# mcu.net
KiCad netlist of a schematic drawn in Altium Designer
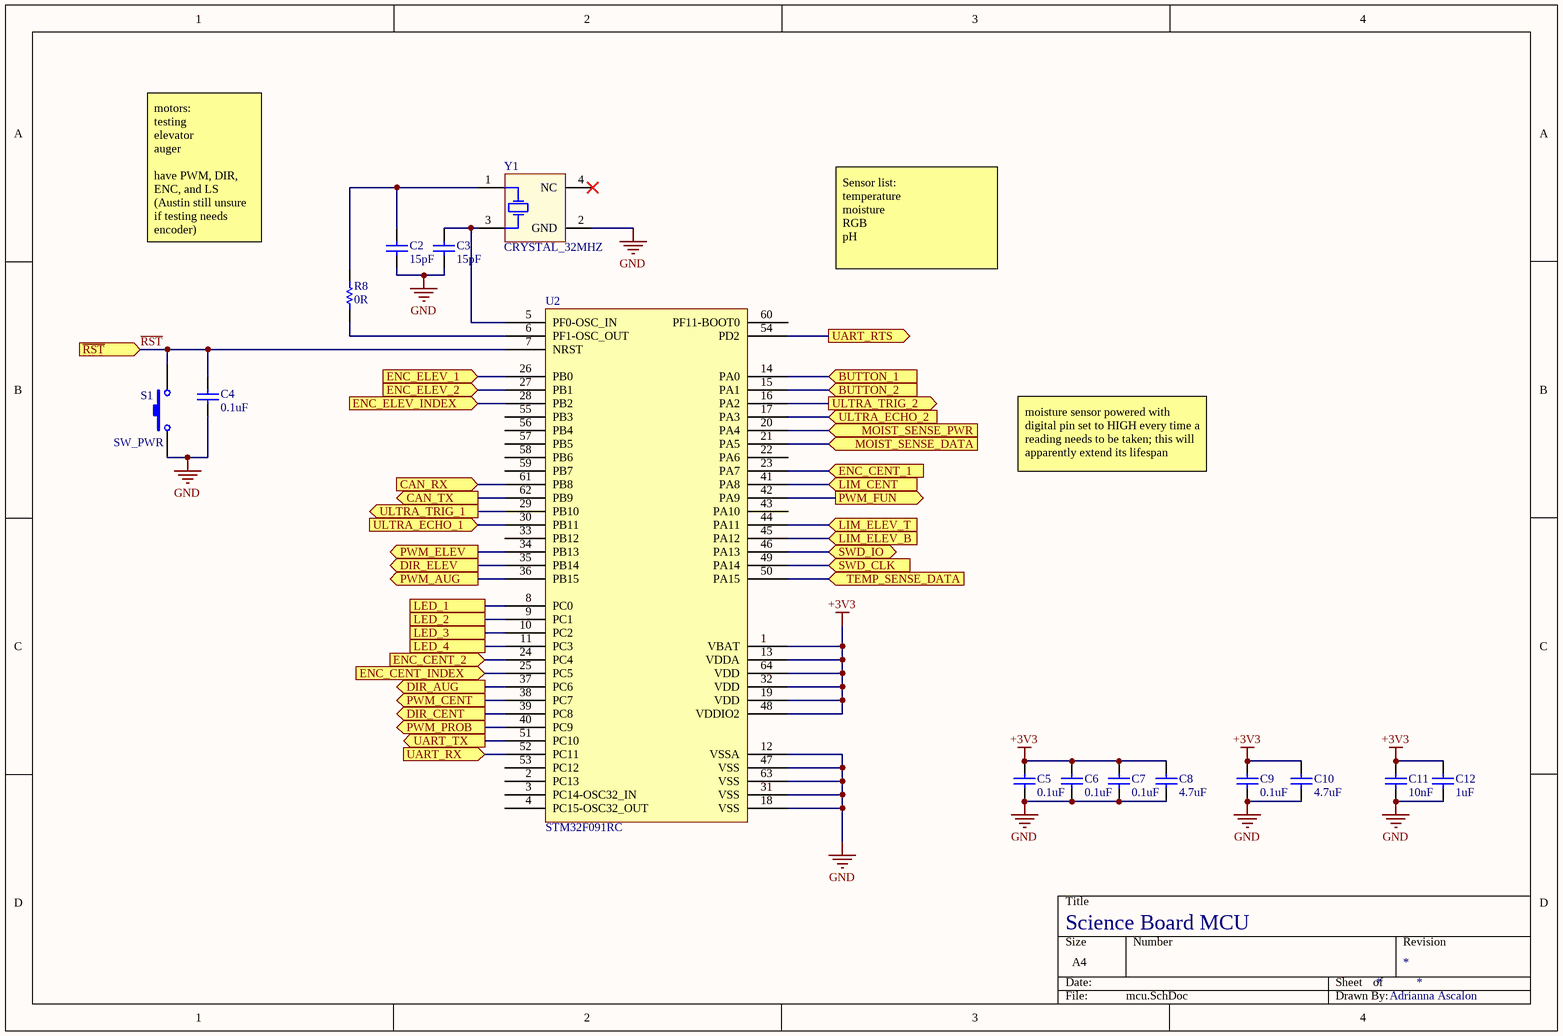
[diagram p0: mcu.SchDoc]

(export (version "E")
  (design (tool "Eeschema 10.0.6"))
  (components
    (comp (ref "C2")
      (value "15pF")
      (footprint "CAPC0603(1608)55_N")
      (description "CAP CER 15PF 250V NPO 0603")
      (fields (field (name "MANUFACTURER") "Yageo") (field (name "MPN") "AC0603JRNPOYBN150"))
      (libsource (lib "UWRT_Schematic_Library_2019") (part "CAP_15pF_0603"))
    )
    (comp (ref "C3")
      (value "15pF")
      (footprint "CAPC0603(1608)55_N")
      (description "CAP CER 15PF 250V NPO 0603")
      (fields (field (name "MANUFACTURER") "Yageo") (field (name "MPN") "AC0603JRNPOYBN150"))
      (libsource (lib "UWRT_Schematic_Library_2019") (part "CAP_15pF_0603"))
    )
    (comp (ref "C4")
      (value "0.1uF")
      (footprint "CAPC0603(1608)55_N")
      (description "CAP CER 0.1UF 16V X7R 0603")
      (fields (field (name "MANUFACTURER") "Yageo") (field (name "MPN") "CC0603KRX7R7BB104"))
      (libsource (lib "UWRT_Schematic_Library_2019") (part "CAP_0.1uF_16V_0603"))
    )
    (comp (ref "C5")
      (value "0.1uF")
      (footprint "CAPC0603(1608)55_N")
      (description "CAP CER 0.1UF 16V X7R 0603")
      (fields (field (name "MANUFACTURER") "Yageo") (field (name "MPN") "CC0603KRX7R7BB104"))
      (libsource (lib "UWRT_Schematic_Library_2019") (part "CAP_0.1uF_16V_0603"))
    )
    (comp (ref "C6")
      (value "0.1uF")
      (footprint "CAPC0603(1608)55_N")
      (description "CAP CER 0.1UF 16V X7R 0603")
      (fields (field (name "MANUFACTURER") "Yageo") (field (name "MPN") "CC0603KRX7R7BB104"))
      (libsource (lib "UWRT_Schematic_Library_2019") (part "CAP_0.1uF_16V_0603"))
    )
    (comp (ref "C7")
      (value "0.1uF")
      (footprint "CAPC0603(1608)55_N")
      (description "CAP CER 0.1UF 16V X7R 0603")
      (fields (field (name "MANUFACTURER") "Yageo") (field (name "MPN") "CC0603KRX7R7BB104"))
      (libsource (lib "UWRT_Schematic_Library_2019") (part "CAP_0.1uF_16V_0603"))
    )
    (comp (ref "C8")
      (value "4.7uF")
      (footprint "CAPC0603(1608)55_N")
      (description "CAP CER 4.7UF 6.3V X5R 0603")
      (fields (field (name "MANUFACTURER") "Yageo") (field (name "MPN") "CC0603KRX5R5BB475"))
      (libsource (lib "UWRT_Schematic_Library_2019") (part "CAP_4.7uF_0603"))
    )
    (comp (ref "C9")
      (value "0.1uF")
      (footprint "CAPC0603(1608)55_N")
      (description "CAP CER 0.1UF 16V X7R 0603")
      (fields (field (name "MANUFACTURER") "Yageo") (field (name "MPN") "CC0603KRX7R7BB104"))
      (libsource (lib "UWRT_Schematic_Library_2019") (part "CAP_0.1uF_16V_0603"))
    )
    (comp (ref "C10")
      (value "4.7uF")
      (footprint "CAPC0603(1608)55_N")
      (description "CAP CER 4.7UF 6.3V X5R 0603")
      (fields (field (name "MANUFACTURER") "Yageo") (field (name "MPN") "CC0603KRX5R5BB475"))
      (libsource (lib "UWRT_Schematic_Library_2019") (part "CAP_4.7uF_0603"))
    )
    (comp (ref "C11")
      (value "10nF")
      (footprint "CAPC0603(1608)55_N")
      (description "CAP CER 10000PF 16V X7R 0603")
      (fields (field (name "MANUFACTURER") "Yageo") (field (name "MPN") "CC0603KRX7R7BB103"))
      (libsource (lib "UWRT_Schematic_Library_2019") (part "CAP_10nF_0603"))
    )
    (comp (ref "C12")
      (value "1uF")
      (footprint "CAPC0603(1608)55_N")
      (description "CAP CER 1UF 16V Y5V 0603")
      (fields (field (name "MANUFACTURER") "Yageo") (field (name "MPN") "CC0603ZRY5V7BB105"))
      (libsource (lib "UWRT_Schematic_Library_2019") (part "CAP_1uF_16V_0603"))
    )
    (comp (ref "R8")
      (value "0R")
      (footprint "RESC0603(1608)_N")
      (description "RES SMD 0 OHM JUMPER 1/10W 0603")
      (fields (field (name "MANUFACTURER") "Yageo") (field (name "MPN") "RC0603JR-070RL"))
      (libsource (lib "UWRT_Schematic_Library_2019") (part "RES_0R_0603"))
    )
    (comp (ref "S1")
      (value "SW_PWR")
      (footprint "PTS830GM140")
      (description "Power Switch (Red)")
      (fields
        (field (name "MPN") "PTS830GM140 SMTR LFS")
        (field (name "DIGIKEY PART NUMBER") "CKN10587CT-ND")
      )
      (libsource (lib "UWRT_Schematic_Library_2019") (part "SW_PWR"))
    )
    (comp (ref "U2")
      (value "STM32F091RC")
      (footprint "UWRT_Footprint_Library_2019:STM_LQFP64_N")
      (fields
        (field (name "MANUFACTURER") "STMicroelectronics")
        (field (name "DIGIKEY PART NUMBER") "497-15167-ND")
      )
      (libsource (lib "UWRT_Schematic_Library_2019") (part "STM32F091RC"))
    )
    (comp (ref "Y1")
      (value "CRYSTAL_32MHZ")
      (footprint "AVX-CX2520DB32000D0GEJZ1-4_V")
      (description "CRYSTAL 32MHZ 8PF SMD")
      (fields
        (field (name "MANUFACTURER") "Kyocera International Inc. Electronic Components")
        (field (name "MPN") "CX2520DB32000D0GPSC1")
      )
      (libsource (lib "UWRT_Schematic_Library_2019") (part "CRYSTAL_32MHZ"))
    )
  )
  (nets
    (net (code "1") (name "+3V3") (class "Default")
      (node (ref "C10") (pin "2") (pinfunction "2_2") (pintype "passive"))
      (node (ref "C11") (pin "2") (pinfunction "2_2") (pintype "passive"))
      (node (ref "C12") (pin "2") (pinfunction "2_2") (pintype "passive"))
      (node (ref "C5") (pin "1") (pinfunction "1_1") (pintype "passive"))
      (node (ref "C6") (pin "1") (pinfunction "1_1") (pintype "passive"))
      (node (ref "C7") (pin "1") (pinfunction "1_1") (pintype "passive"))
      (node (ref "C8") (pin "2") (pinfunction "2_2") (pintype "passive"))
      (node (ref "C9") (pin "1") (pinfunction "1_1") (pintype "passive"))
      (node (ref "U2") (pin "1") (pinfunction "VBAT_1") (pintype "passive"))
      (node (ref "U2") (pin "13") (pinfunction "VDDA_13") (pintype "passive"))
      (node (ref "U2") (pin "19") (pinfunction "VDD_19") (pintype "passive"))
      (node (ref "U2") (pin "32") (pinfunction "VDD_32") (pintype "passive"))
      (node (ref "U2") (pin "48") (pinfunction "VDDIO2_48") (pintype "passive"))
      (node (ref "U2") (pin "64") (pinfunction "VDD_64") (pintype "passive"))
    )
    (net (code "2") (name "/BUTTON_1") (class "Default")
      (node (ref "U2") (pin "14") (pinfunction "PA0_14") (pintype "passive"))
    )
    (net (code "3") (name "/BUTTON_2") (class "Default")
      (node (ref "U2") (pin "15") (pinfunction "PA1_15") (pintype "passive"))
    )
    (net (code "4") (name "/CAN_RX") (class "Default")
      (node (ref "U2") (pin "61") (pinfunction "PB8_61") (pintype "passive"))
    )
    (net (code "5") (name "/CAN_TX") (class "Default")
      (node (ref "U2") (pin "62") (pinfunction "PB9_62") (pintype "passive"))
    )
    (net (code "6") (name "/DIR_AUG") (class "Default")
      (node (ref "U2") (pin "37") (pinfunction "PC6_37") (pintype "passive"))
    )
    (net (code "7") (name "/DIR_CENT") (class "Default")
      (node (ref "U2") (pin "39") (pinfunction "PC8_39") (pintype "passive"))
    )
    (net (code "8") (name "/DIR_ELEV") (class "Default")
      (node (ref "U2") (pin "35") (pinfunction "PB14_35") (pintype "passive"))
    )
    (net (code "9") (name "/ENC_CENT_1") (class "Default")
      (node (ref "U2") (pin "23") (pinfunction "PA7_23") (pintype "passive"))
    )
    (net (code "10") (name "/ENC_CENT_2") (class "Default")
      (node (ref "U2") (pin "24") (pinfunction "PC4_24") (pintype "passive"))
    )
    (net (code "11") (name "/ENC_CENT_INDEX") (class "Default")
      (node (ref "U2") (pin "25") (pinfunction "PC5_25") (pintype "passive"))
    )
    (net (code "12") (name "/ENC_ELEV_1") (class "Default")
      (node (ref "U2") (pin "26") (pinfunction "PB0_26") (pintype "passive"))
    )
    (net (code "13") (name "/ENC_ELEV_2") (class "Default")
      (node (ref "U2") (pin "27") (pinfunction "PB1_27") (pintype "passive"))
    )
    (net (code "14") (name "/ENC_ELEV_INDEX") (class "Default")
      (node (ref "U2") (pin "28") (pinfunction "PB2_28") (pintype "passive"))
    )
    (net (code "15") (name "/LED_1") (class "Default")
      (node (ref "U2") (pin "8") (pinfunction "PC0_8") (pintype "passive"))
    )
    (net (code "16") (name "/LED_2") (class "Default")
      (node (ref "U2") (pin "9") (pinfunction "PC1_9") (pintype "passive"))
    )
    (net (code "17") (name "/LED_3") (class "Default")
      (node (ref "U2") (pin "10") (pinfunction "PC2_10") (pintype "passive"))
    )
    (net (code "18") (name "/LED_4") (class "Default")
      (node (ref "U2") (pin "11") (pinfunction "PC3_11") (pintype "passive"))
    )
    (net (code "19") (name "/LIM_CENT") (class "Default")
      (node (ref "U2") (pin "41") (pinfunction "PA8_41") (pintype "passive"))
    )
    (net (code "20") (name "/LIM_ELEV_B") (class "Default")
      (node (ref "U2") (pin "45") (pinfunction "PA12_45") (pintype "passive"))
    )
    (net (code "21") (name "/LIM_ELEV_T") (class "Default")
      (node (ref "U2") (pin "44") (pinfunction "PA11_44") (pintype "passive"))
    )
    (net (code "22") (name "/MOIST_SENSE_DATA") (class "Default")
      (node (ref "U2") (pin "21") (pinfunction "PA5_21") (pintype "passive"))
    )
    (net (code "23") (name "/MOIST_SENSE_PWR") (class "Default")
      (node (ref "U2") (pin "20") (pinfunction "PA4_20") (pintype "passive"))
    )
    (net (code "24") (name "/PWM_AUG") (class "Default")
      (node (ref "U2") (pin "36") (pinfunction "PB15_36") (pintype "passive"))
    )
    (net (code "25") (name "/PWM_CENT") (class "Default")
      (node (ref "U2") (pin "38") (pinfunction "PC7_38") (pintype "passive"))
    )
    (net (code "26") (name "/PWM_ELEV") (class "Default")
      (node (ref "U2") (pin "34") (pinfunction "PB13_34") (pintype "passive"))
    )
    (net (code "27") (name "/PWM_FUN") (class "Default")
      (node (ref "U2") (pin "42") (pinfunction "PA9_42") (pintype "passive"))
    )
    (net (code "28") (name "/PWM_PROB") (class "Default")
      (node (ref "U2") (pin "40") (pinfunction "PC9_40") (pintype "passive"))
    )
    (net (code "29") (name "/SWD_CLK") (class "Default")
      (node (ref "U2") (pin "49") (pinfunction "PA14_49") (pintype "passive"))
    )
    (net (code "30") (name "/SWD_IO") (class "Default")
      (node (ref "U2") (pin "46") (pinfunction "PA13_46") (pintype "passive"))
    )
    (net (code "31") (name "/TEMP_SENSE_DATA") (class "Default")
      (node (ref "U2") (pin "50") (pinfunction "PA15_50") (pintype "passive"))
    )
    (net (code "32") (name "/UART_RTS") (class "Default")
      (node (ref "U2") (pin "54") (pinfunction "PD2_54") (pintype "passive"))
    )
    (net (code "33") (name "/UART_RX") (class "Default")
      (node (ref "U2") (pin "52") (pinfunction "PC11_52") (pintype "passive"))
    )
    (net (code "34") (name "/UART_TX") (class "Default")
      (node (ref "U2") (pin "51") (pinfunction "PC10_51") (pintype "passive"))
    )
    (net (code "35") (name "/ULTRA_ECHO_1") (class "Default")
      (node (ref "U2") (pin "30") (pinfunction "PB11_30") (pintype "passive"))
    )
    (net (code "36") (name "/ULTRA_ECHO_2") (class "Default")
      (node (ref "U2") (pin "17") (pinfunction "PA3_17") (pintype "passive"))
    )
    (net (code "37") (name "/ULTRA_TRIG_1") (class "Default")
      (node (ref "U2") (pin "29") (pinfunction "PB10_29") (pintype "passive"))
    )
    (net (code "38") (name "/ULTRA_TRIG_2") (class "Default")
      (node (ref "U2") (pin "16") (pinfunction "PA2_16") (pintype "passive"))
    )
    (net (code "39") (name "/~{RST}") (class "Default")
      (node (ref "C4") (pin "2") (pinfunction "2_2") (pintype "passive"))
      (node (ref "S1") (pin "2") (pinfunction "2_2") (pintype "passive"))
      (node (ref "U2") (pin "7") (pinfunction "NRST_7") (pintype "passive"))
    )
    (net (code "40") (name "GND") (class "Default")
      (node (ref "C10") (pin "1") (pinfunction "1_1") (pintype "passive"))
      (node (ref "C11") (pin "1") (pinfunction "1_1") (pintype "passive"))
      (node (ref "C12") (pin "1") (pinfunction "1_1") (pintype "passive"))
      (node (ref "C2") (pin "1") (pinfunction "1_1") (pintype "passive"))
      (node (ref "C3") (pin "1") (pinfunction "1_1") (pintype "passive"))
      (node (ref "C4") (pin "1") (pinfunction "1_1") (pintype "passive"))
      (node (ref "C5") (pin "2") (pinfunction "2_2") (pintype "passive"))
      (node (ref "C6") (pin "2") (pinfunction "2_2") (pintype "passive"))
      (node (ref "C7") (pin "2") (pinfunction "2_2") (pintype "passive"))
      (node (ref "C8") (pin "1") (pinfunction "1_1") (pintype "passive"))
      (node (ref "C9") (pin "2") (pinfunction "2_2") (pintype "passive"))
      (node (ref "S1") (pin "1") (pinfunction "1_1") (pintype "passive"))
      (node (ref "U2") (pin "12") (pinfunction "VSSA_12") (pintype "passive"))
      (node (ref "U2") (pin "18") (pinfunction "VSS_18") (pintype "passive"))
      (node (ref "U2") (pin "31") (pinfunction "VSS_31") (pintype "passive"))
      (node (ref "U2") (pin "47") (pinfunction "VSS_47") (pintype "passive"))
      (node (ref "U2") (pin "63") (pinfunction "VSS_63") (pintype "passive"))
      (node (ref "Y1") (pin "2") (pinfunction "GND_2") (pintype "power_in"))
    )
    (net (code "41") (name "Net-(C2-Pad2)") (class "Default")
      (node (ref "C2") (pin "2") (pinfunction "2_2") (pintype "passive"))
      (node (ref "R8") (pin "2") (pinfunction "2_2") (pintype "passive"))
      (node (ref "Y1") (pin "1") (pinfunction "HOT_1") (pintype "passive"))
    )
    (net (code "42") (name "Net-(U2-PF0-OSC_IN)") (class "Default")
      (node (ref "C3") (pin "2") (pinfunction "2_2") (pintype "passive"))
      (node (ref "U2") (pin "5") (pinfunction "PF0-OSC_IN_5") (pintype "passive"))
      (node (ref "Y1") (pin "3") (pinfunction "HOT_3") (pintype "passive"))
    )
    (net (code "43") (name "Net-(U2-PF1-OSC_OUT)") (class "Default")
      (node (ref "R8") (pin "1") (pinfunction "1_1") (pintype "passive"))
      (node (ref "U2") (pin "6") (pinfunction "PF1-OSC_OUT_6") (pintype "passive"))
    )
    (net (code "44") (name "unconnected-(U2-PA6-Pad22)") (class "Default")
      (node (ref "U2") (pin "22") (pinfunction "PA6_22") (pintype "passive"))
    )
    (net (code "45") (name "unconnected-(U2-PA10-Pad43)") (class "Default")
      (node (ref "U2") (pin "43") (pinfunction "PA10_43") (pintype "passive"))
    )
    (net (code "46") (name "unconnected-(U2-PB3-Pad55)") (class "Default")
      (node (ref "U2") (pin "55") (pinfunction "PB3_55") (pintype "passive"))
    )
    (net (code "47") (name "unconnected-(U2-PB4-Pad56)") (class "Default")
      (node (ref "U2") (pin "56") (pinfunction "PB4_56") (pintype "passive"))
    )
    (net (code "48") (name "unconnected-(U2-PB5-Pad57)") (class "Default")
      (node (ref "U2") (pin "57") (pinfunction "PB5_57") (pintype "passive"))
    )
    (net (code "49") (name "unconnected-(U2-PB6-Pad58)") (class "Default")
      (node (ref "U2") (pin "58") (pinfunction "PB6_58") (pintype "passive"))
    )
    (net (code "50") (name "unconnected-(U2-PB7-Pad59)") (class "Default")
      (node (ref "U2") (pin "59") (pinfunction "PB7_59") (pintype "passive"))
    )
    (net (code "51") (name "unconnected-(U2-PB12-Pad33)") (class "Default")
      (node (ref "U2") (pin "33") (pinfunction "PB12_33") (pintype "passive"))
    )
    (net (code "52") (name "unconnected-(U2-PC12-Pad53)") (class "Default")
      (node (ref "U2") (pin "53") (pinfunction "PC12_53") (pintype "passive"))
    )
    (net (code "53") (name "unconnected-(U2-PC13-Pad2)") (class "Default")
      (node (ref "U2") (pin "2") (pinfunction "PC13_2") (pintype "passive"))
    )
    (net (code "54") (name "unconnected-(U2-PC14-OSC32_IN-Pad3)") (class "Default")
      (node (ref "U2") (pin "3") (pinfunction "PC14-OSC32_IN_3") (pintype "passive"))
    )
    (net (code "55") (name "unconnected-(U2-PC15-OSC32_OUT-Pad4)") (class "Default")
      (node (ref "U2") (pin "4") (pinfunction "PC15-OSC32_OUT_4") (pintype "passive"))
    )
    (net (code "56") (name "unconnected-(U2-PF11-BOOT0-Pad60)") (class "Default")
      (node (ref "U2") (pin "60") (pinfunction "PF11-BOOT0_60") (pintype "passive"))
    )
    (net (code "57") (name "unconnected-(Y1-NC-Pad4)") (class "Default")
      (node (ref "Y1") (pin "4") (pinfunction "NC_4") (pintype "passive+no_connect"))
    )
  )
)
